# hd-gs-alt.net
KiCad netlist of a schematic drawn in EAGLE
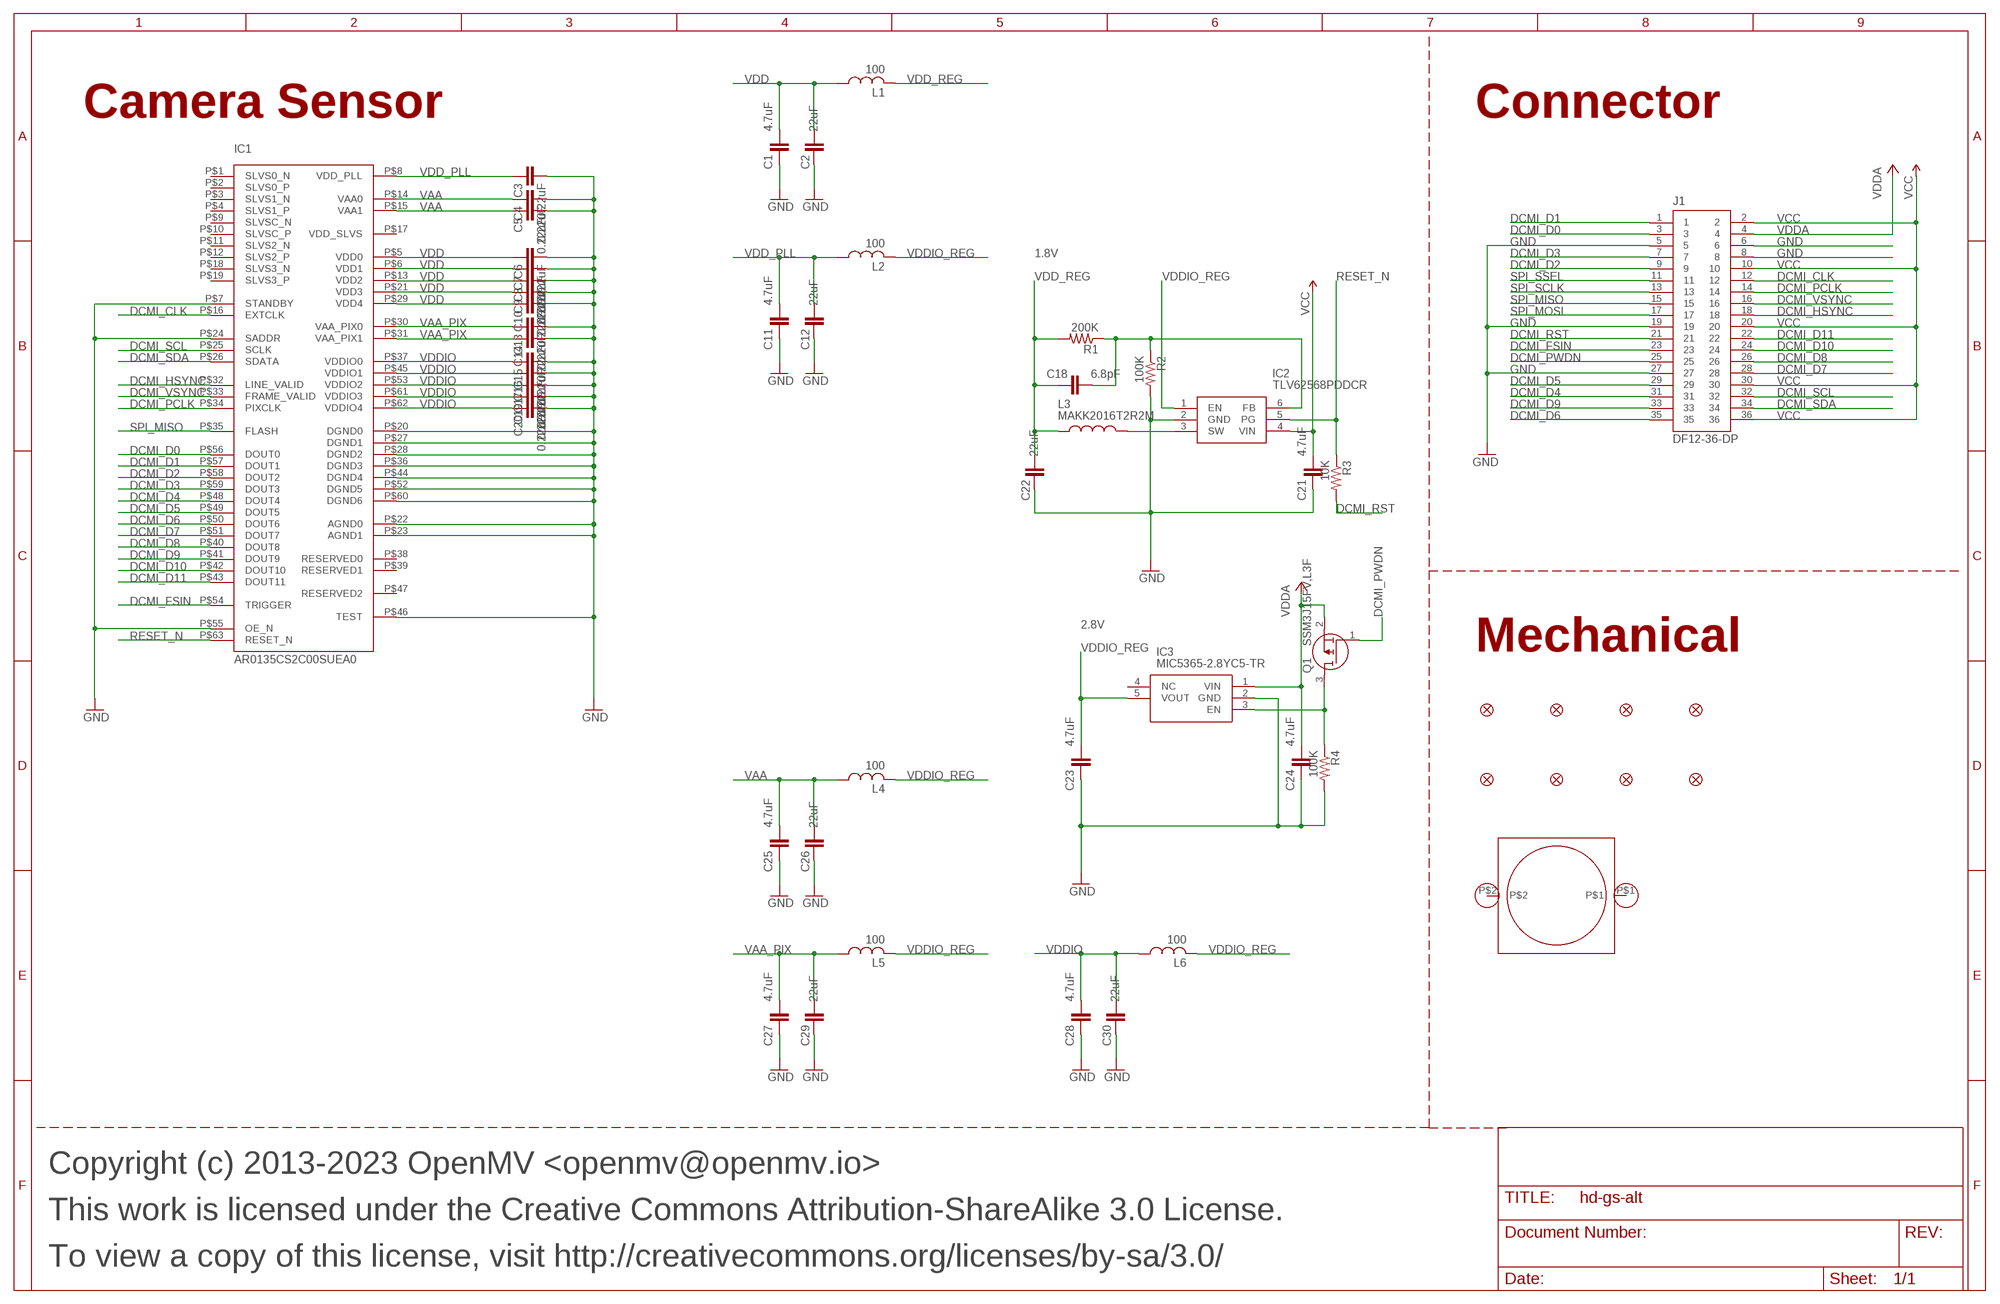
[diagram p0: schematic, sheet 1]

(export (version "E")
  (design (tool "Eeschema 10.0.6"))
  (components
    (comp (ref "C1")
      (value "4.7uF")
      (footprint "eagle-import:0402")
      (fields (field (name "MPN") "JMK105BBJ475MV-F"))
      (libsource (lib "eagle-import") (part "CAP_0402"))
    )
    (comp (ref "C2")
      (value "22uF")
      (footprint "eagle-import:0805")
      (fields (field (name "MPN") "CL21A226MQQNNNE"))
      (libsource (lib "eagle-import") (part "22UF-0805-6.3V-20%"))
    )
    (comp (ref "C3")
      (value "0.22uF")
      (footprint "eagle-import:C0201")
      (fields (field (name "MPN") "GRM033R60J224ME15D"))
      (libsource (lib "eagle-import") (part "C-EUC0201"))
    )
    (comp (ref "C4")
      (value "0.22uF")
      (footprint "eagle-import:C0201")
      (fields (field (name "MPN") "GRM033R60J224ME15D"))
      (libsource (lib "eagle-import") (part "C-EUC0201"))
    )
    (comp (ref "C5")
      (value "0.22uF")
      (footprint "eagle-import:C0201")
      (fields (field (name "MPN") "GRM033R60J224ME15D"))
      (libsource (lib "eagle-import") (part "C-EUC0201"))
    )
    (comp (ref "C6")
      (value "0.22uF")
      (footprint "eagle-import:C0201")
      (fields (field (name "MPN") "GRM033R60J224ME15D"))
      (libsource (lib "eagle-import") (part "C-EUC0201"))
    )
    (comp (ref "C7")
      (value "0.22uF")
      (footprint "eagle-import:C0201")
      (fields (field (name "MPN") "GRM033R60J224ME15D"))
      (libsource (lib "eagle-import") (part "C-EUC0201"))
    )
    (comp (ref "C8")
      (value "0.22uF")
      (footprint "eagle-import:C0201")
      (fields (field (name "MPN") "GRM033R60J224ME15D"))
      (libsource (lib "eagle-import") (part "C-EUC0201"))
    )
    (comp (ref "C9")
      (value "0.22uF")
      (footprint "eagle-import:C0201")
      (fields (field (name "MPN") "GRM033R60J224ME15D"))
      (libsource (lib "eagle-import") (part "C-EUC0201"))
    )
    (comp (ref "C10")
      (value "0.22uF")
      (footprint "eagle-import:C0201")
      (fields (field (name "MPN") "GRM033R60J224ME15D"))
      (libsource (lib "eagle-import") (part "C-EUC0201"))
    )
    (comp (ref "C11")
      (value "4.7uF")
      (footprint "eagle-import:0402")
      (fields (field (name "MPN") "JMK105BBJ475MV-F"))
      (libsource (lib "eagle-import") (part "CAP_0402"))
    )
    (comp (ref "C12")
      (value "22uF")
      (footprint "eagle-import:0805")
      (fields (field (name "MPN") "CL21A226MQQNNNE"))
      (libsource (lib "eagle-import") (part "22UF-0805-6.3V-20%"))
    )
    (comp (ref "C13")
      (value "0.22uF")
      (footprint "eagle-import:C0201")
      (fields (field (name "MPN") "GRM033R60J224ME15D"))
      (libsource (lib "eagle-import") (part "C-EUC0201"))
    )
    (comp (ref "C14")
      (value "0.22uF")
      (footprint "eagle-import:C0201")
      (fields (field (name "MPN") "GRM033R60J224ME15D"))
      (libsource (lib "eagle-import") (part "C-EUC0201"))
    )
    (comp (ref "C15")
      (value "0.22uF")
      (footprint "eagle-import:C0201")
      (fields (field (name "MPN") "GRM033R60J224ME15D"))
      (libsource (lib "eagle-import") (part "C-EUC0201"))
    )
    (comp (ref "C16")
      (value "0.22uF")
      (footprint "eagle-import:C0201")
      (fields (field (name "MPN") "GRM033R60J224ME15D"))
      (libsource (lib "eagle-import") (part "C-EUC0201"))
    )
    (comp (ref "C17")
      (value "0.22uF")
      (footprint "eagle-import:C0201")
      (fields (field (name "MPN") "GRM033R60J224ME15D"))
      (libsource (lib "eagle-import") (part "C-EUC0201"))
    )
    (comp (ref "C18")
      (value "6.8pF")
      (footprint "eagle-import:0402")
      (fields (field (name "MPN") "GRM1555C1H6R8DA01D"))
      (libsource (lib "eagle-import") (part "CAP_0402"))
    )
    (comp (ref "C19")
      (value "0.22uF")
      (footprint "eagle-import:C0201")
      (fields (field (name "MPN") "GRM033R60J224ME15D"))
      (libsource (lib "eagle-import") (part "C-EUC0201"))
    )
    (comp (ref "C20")
      (value "0.22uF")
      (footprint "eagle-import:C0201")
      (fields (field (name "MPN") "GRM033R60J224ME15D"))
      (libsource (lib "eagle-import") (part "C-EUC0201"))
    )
    (comp (ref "C21")
      (value "4.7uF")
      (footprint "eagle-import:0402")
      (fields (field (name "MPN") "JMK105BBJ475MV-F"))
      (libsource (lib "eagle-import") (part "CAP_0402"))
    )
    (comp (ref "C22")
      (value "22uF")
      (footprint "eagle-import:0805")
      (fields (field (name "MPN") "CL21A226MQQNNNE"))
      (libsource (lib "eagle-import") (part "22UF-0805-6.3V-20%"))
    )
    (comp (ref "C23")
      (value "4.7uF")
      (footprint "eagle-import:0402")
      (fields (field (name "MPN") "JMK105BBJ475MV-F"))
      (libsource (lib "eagle-import") (part "CAP_0402"))
    )
    (comp (ref "C24")
      (value "4.7uF")
      (footprint "eagle-import:0402")
      (fields (field (name "MPN") "JMK105BBJ475MV-F"))
      (libsource (lib "eagle-import") (part "CAP_0402"))
    )
    (comp (ref "C25")
      (value "4.7uF")
      (footprint "eagle-import:0402")
      (fields (field (name "MPN") "JMK105BBJ475MV-F"))
      (libsource (lib "eagle-import") (part "CAP_0402"))
    )
    (comp (ref "C26")
      (value "22uF")
      (footprint "eagle-import:0805")
      (fields (field (name "MPN") "CL21A226MQQNNNE"))
      (libsource (lib "eagle-import") (part "22UF-0805-6.3V-20%"))
    )
    (comp (ref "C27")
      (value "4.7uF")
      (footprint "eagle-import:0402")
      (fields (field (name "MPN") "JMK105BBJ475MV-F"))
      (libsource (lib "eagle-import") (part "CAP_0402"))
    )
    (comp (ref "C28")
      (value "4.7uF")
      (footprint "eagle-import:0402")
      (fields (field (name "MPN") "JMK105BBJ475MV-F"))
      (libsource (lib "eagle-import") (part "CAP_0402"))
    )
    (comp (ref "C29")
      (value "22uF")
      (footprint "eagle-import:0805")
      (fields (field (name "MPN") "CL21A226MQQNNNE"))
      (libsource (lib "eagle-import") (part "22UF-0805-6.3V-20%"))
    )
    (comp (ref "C30")
      (value "22uF")
      (footprint "eagle-import:0805")
      (fields (field (name "MPN") "CL21A226MQQNNNE"))
      (libsource (lib "eagle-import") (part "22UF-0805-6.3V-20%"))
    )
    (comp (ref "FD1")
      (value "FIDUCIAL1X2")
      (footprint "eagle-import:FIDUCIAL-1X2")
      (libsource (lib "eagle-import") (part "FIDUCIAL1X2"))
    )
    (comp (ref "FD2")
      (value "FIDUCIAL1X2")
      (footprint "eagle-import:FIDUCIAL-1X2")
      (libsource (lib "eagle-import") (part "FIDUCIAL1X2"))
    )
    (comp (ref "FD3")
      (value "FIDUCIAL1X2")
      (footprint "eagle-import:FIDUCIAL-1X2")
      (libsource (lib "eagle-import") (part "FIDUCIAL1X2"))
    )
    (comp (ref "FD4")
      (value "FIDUCIAL1X2")
      (footprint "eagle-import:FIDUCIAL-1X2")
      (libsource (lib "eagle-import") (part "FIDUCIAL1X2"))
    )
    (comp (ref "FD5")
      (value "FIDUCIAL1X2")
      (footprint "eagle-import:FIDUCIAL-1X2")
      (libsource (lib "eagle-import") (part "FIDUCIAL1X2"))
    )
    (comp (ref "FD6")
      (value "FIDUCIAL1X2")
      (footprint "eagle-import:FIDUCIAL-1X2")
      (libsource (lib "eagle-import") (part "FIDUCIAL1X2"))
    )
    (comp (ref "FD7")
      (value "FIDUCIAL1X2")
      (footprint "eagle-import:FIDUCIAL-1X2")
      (libsource (lib "eagle-import") (part "FIDUCIAL1X2"))
    )
    (comp (ref "FD8")
      (value "FIDUCIAL1X2")
      (footprint "eagle-import:FIDUCIAL-1X2")
      (libsource (lib "eagle-import") (part "FIDUCIAL1X2"))
    )
    (comp (ref "H1")
      (value "LENSMOUNT20MM")
      (footprint "eagle-import:LENSMOUNT-20MM")
      (libsource (lib "eagle-import") (part "LENSMOUNT20MM"))
    )
    (comp (ref "IC1")
      (value "AR0135CS2C00SUEA0")
      (footprint "eagle-import:AR0135CS2C00SUEA0")
      (fields (field (name "MPN") "AR0135CS2C00SUEA0-DRBR"))
      (libsource (lib "eagle-import") (part "AR0135CS2C00SUEA0"))
    )
    (comp (ref "IC2")
      (value "TLV62568PDDCR")
      (footprint "eagle-import:SOT95P280X110-6N")
      (fields (field (name "MOUSER_PART_NUMBER") "595-TLV62568PDDCR"))
      (libsource (lib "eagle-import") (part "TLV62568PDDCR"))
    )
    (comp (ref "IC3")
      (value "MIC5365-2.8YC5-TR")
      (footprint "eagle-import:SOT65P210X110-5N")
      (fields (field (name "MOUSER_PART_NUMBER") "998-MIC5365-2.8YC5TR"))
      (libsource (lib "eagle-import") (part "MIC5365-2.8YC5-TR"))
    )
    (comp (ref "J1")
      (value "DF12-36-DP")
      (footprint "eagle-import:DF12-36-DP")
      (fields (field (name "MPN") "DF12NB(3.0)-36DP-0.5V(51)"))
      (libsource (lib "eagle-import") (part "DF12-36-DP"))
    )
    (comp (ref "L1")
      (value "100")
      (footprint "eagle-import:0402")
      (fields (field (name "MPN") "MFBM1V1005-101-R"))
      (libsource (lib "eagle-import") (part "INDUCTOR_0402"))
    )
    (comp (ref "L2")
      (value "100")
      (footprint "eagle-import:0402")
      (fields (field (name "MPN") "MFBM1V1005-101-R"))
      (libsource (lib "eagle-import") (part "INDUCTOR_0402"))
    )
    (comp (ref "L3")
      (value "MAKK2016T2R2M")
      (footprint "eagle-import:INDC2016X100N")
      (fields (field (name "MF") "Taiyo Yuden"))
      (libsource (lib "eagle-import") (part "MAKK2016T2R2M"))
    )
    (comp (ref "L4")
      (value "100")
      (footprint "eagle-import:0402")
      (fields (field (name "MPN") "MFBM1V1005-101-R"))
      (libsource (lib "eagle-import") (part "INDUCTOR_0402"))
    )
    (comp (ref "L5")
      (value "100")
      (footprint "eagle-import:0402")
      (fields (field (name "MPN") "MFBM1V1005-101-R"))
      (libsource (lib "eagle-import") (part "INDUCTOR_0402"))
    )
    (comp (ref "L6")
      (value "100")
      (footprint "eagle-import:0402")
      (fields (field (name "MPN") "MFBM1V1005-101-R"))
      (libsource (lib "eagle-import") (part "INDUCTOR_0402"))
    )
    (comp (ref "Q1")
      (value "SSM3J15FV,L3F")
      (footprint "eagle-import:SSM3J15FVL3F")
      (fields (field (name "MOUSER_PART_NUMBER") "757-SSM3J15FVL3F"))
      (libsource (lib "eagle-import") (part "SSM3J15FV,L3F"))
    )
    (comp (ref "R1")
      (value "200K")
      (footprint "eagle-import:R0402")
      (fields (field (name "MPN") "CRCW0402200KFKEDC"))
      (libsource (lib "eagle-import") (part "R-US_R0402"))
    )
    (comp (ref "R2")
      (value "100K")
      (footprint "eagle-import:R0402")
      (fields (field (name "MPN") "AC0402FR-07100KL"))
      (libsource (lib "eagle-import") (part "R-US_R0402"))
    )
    (comp (ref "R3")
      (value "10K")
      (footprint "eagle-import:R0402")
      (fields (field (name "MPN") "AC0402FR-1310KL"))
      (libsource (lib "eagle-import") (part "R-US_R0402"))
    )
    (comp (ref "R4")
      (value "100K")
      (footprint "eagle-import:R0402")
      (fields (field (name "MPN") "AC0402FR-07100KL"))
      (libsource (lib "eagle-import") (part "R-US_R0402"))
    )
  )
  (nets
    (net (code "1") (name "/DCMI_CLK") (class "Default")
      (node (ref "IC1") (pin "P$16") (pinfunction "EXTCLK_P$16") (pintype "bidirectional"))
      (node (ref "J1") (pin "12") (pinfunction "12_12") (pintype "bidirectional"))
    )
    (net (code "2") (name "/DCMI_D0") (class "Default")
      (node (ref "IC1") (pin "P$56") (pinfunction "DOUT0_P$56") (pintype "bidirectional"))
      (node (ref "J1") (pin "3") (pinfunction "3_3") (pintype "bidirectional"))
    )
    (net (code "3") (name "/DCMI_D1") (class "Default")
      (node (ref "IC1") (pin "P$57") (pinfunction "DOUT1_P$57") (pintype "bidirectional"))
      (node (ref "J1") (pin "1") (pinfunction "1_1") (pintype "bidirectional"))
    )
    (net (code "4") (name "/DCMI_D2") (class "Default")
      (node (ref "IC1") (pin "P$58") (pinfunction "DOUT2_P$58") (pintype "bidirectional"))
      (node (ref "J1") (pin "9") (pinfunction "9_9") (pintype "bidirectional"))
    )
    (net (code "5") (name "/DCMI_D3") (class "Default")
      (node (ref "IC1") (pin "P$59") (pinfunction "DOUT3_P$59") (pintype "bidirectional"))
      (node (ref "J1") (pin "7") (pinfunction "7_7") (pintype "bidirectional"))
    )
    (net (code "6") (name "/DCMI_D4") (class "Default")
      (node (ref "IC1") (pin "P$48") (pinfunction "DOUT4_P$48") (pintype "bidirectional"))
      (node (ref "J1") (pin "31") (pinfunction "31_31") (pintype "bidirectional"))
    )
    (net (code "7") (name "/DCMI_D5") (class "Default")
      (node (ref "IC1") (pin "P$49") (pinfunction "DOUT5_P$49") (pintype "bidirectional"))
      (node (ref "J1") (pin "29") (pinfunction "29_29") (pintype "bidirectional"))
    )
    (net (code "8") (name "/DCMI_D6") (class "Default")
      (node (ref "IC1") (pin "P$50") (pinfunction "DOUT6_P$50") (pintype "bidirectional"))
      (node (ref "J1") (pin "35") (pinfunction "35_35") (pintype "bidirectional"))
    )
    (net (code "9") (name "/DCMI_D7") (class "Default")
      (node (ref "IC1") (pin "P$51") (pinfunction "DOUT7_P$51") (pintype "bidirectional"))
      (node (ref "J1") (pin "28") (pinfunction "28_28") (pintype "bidirectional"))
    )
    (net (code "10") (name "/DCMI_D8") (class "Default")
      (node (ref "IC1") (pin "P$40") (pinfunction "DOUT8_P$40") (pintype "bidirectional"))
      (node (ref "J1") (pin "26") (pinfunction "26_26") (pintype "bidirectional"))
    )
    (net (code "11") (name "/DCMI_D9") (class "Default")
      (node (ref "IC1") (pin "P$41") (pinfunction "DOUT9_P$41") (pintype "bidirectional"))
      (node (ref "J1") (pin "33") (pinfunction "33_33") (pintype "bidirectional"))
    )
    (net (code "12") (name "/DCMI_D10") (class "Default")
      (node (ref "IC1") (pin "P$42") (pinfunction "DOUT10_P$42") (pintype "bidirectional"))
      (node (ref "J1") (pin "24") (pinfunction "24_24") (pintype "bidirectional"))
    )
    (net (code "13") (name "/DCMI_D11") (class "Default")
      (node (ref "IC1") (pin "P$43") (pinfunction "DOUT11_P$43") (pintype "bidirectional"))
      (node (ref "J1") (pin "22") (pinfunction "22_22") (pintype "bidirectional"))
    )
    (net (code "14") (name "/DCMI_FSIN") (class "Default")
      (node (ref "IC1") (pin "P$54") (pinfunction "TRIGGER_P$54") (pintype "bidirectional"))
      (node (ref "J1") (pin "23") (pinfunction "23_23") (pintype "bidirectional"))
    )
    (net (code "15") (name "/DCMI_HSYNC") (class "Default")
      (node (ref "IC1") (pin "P$32") (pinfunction "LINE_VALID_P$32") (pintype "bidirectional"))
      (node (ref "J1") (pin "18") (pinfunction "18_18") (pintype "bidirectional"))
    )
    (net (code "16") (name "/DCMI_PCLK") (class "Default")
      (node (ref "IC1") (pin "P$34") (pinfunction "PIXCLK_P$34") (pintype "bidirectional"))
      (node (ref "J1") (pin "14") (pinfunction "14_14") (pintype "bidirectional"))
    )
    (net (code "17") (name "/DCMI_PWDN") (class "Default")
      (node (ref "J1") (pin "25") (pinfunction "25_25") (pintype "bidirectional"))
      (node (ref "Q1") (pin "1") (pinfunction "G_1") (pintype "bidirectional"))
    )
    (net (code "18") (name "/DCMI_RST") (class "Default")
      (node (ref "J1") (pin "21") (pinfunction "21_21") (pintype "bidirectional"))
      (node (ref "R3") (pin "2") (pinfunction "2_2") (pintype "passive"))
    )
    (net (code "19") (name "/DCMI_SCL") (class "Default")
      (node (ref "IC1") (pin "P$25") (pinfunction "SCLK_P$25") (pintype "bidirectional"))
      (node (ref "J1") (pin "32") (pinfunction "32_32") (pintype "bidirectional"))
    )
    (net (code "20") (name "/DCMI_SDA") (class "Default")
      (node (ref "IC1") (pin "P$26") (pinfunction "SDATA_P$26") (pintype "bidirectional"))
      (node (ref "J1") (pin "34") (pinfunction "34_34") (pintype "bidirectional"))
    )
    (net (code "21") (name "/DCMI_VSYNC") (class "Default")
      (node (ref "IC1") (pin "P$33") (pinfunction "FRAME_VALID_P$33") (pintype "bidirectional"))
      (node (ref "J1") (pin "16") (pinfunction "16_16") (pintype "bidirectional"))
    )
    (net (code "22") (name "/P$1") (class "Default")
      (node (ref "H1") (pin "P$1") (pinfunction "P$1_P$1") (pintype "power_in"))
    )
    (net (code "23") (name "/P$2") (class "Default")
      (node (ref "H1") (pin "P$2") (pinfunction "P$2_P$2") (pintype "power_in"))
    )
    (net (code "24") (name "/RESET_N") (class "Default")
      (node (ref "IC1") (pin "P$63") (pinfunction "RESET_N_P$63") (pintype "bidirectional"))
      (node (ref "IC2") (pin "5") (pinfunction "PG_5") (pintype "bidirectional"))
      (node (ref "R3") (pin "1") (pinfunction "1_1") (pintype "passive"))
    )
    (net (code "25") (name "/SPI_MISO") (class "Default")
      (node (ref "IC1") (pin "P$35") (pinfunction "FLASH_P$35") (pintype "bidirectional"))
      (node (ref "J1") (pin "15") (pinfunction "15_15") (pintype "bidirectional"))
    )
    (net (code "26") (name "/SPI_MOSI") (class "Default")
      (node (ref "J1") (pin "17") (pinfunction "17_17") (pintype "bidirectional"))
    )
    (net (code "27") (name "/SPI_SCLK") (class "Default")
      (node (ref "J1") (pin "13") (pinfunction "13_13") (pintype "bidirectional"))
    )
    (net (code "28") (name "/SPI_SSEL") (class "Default")
      (node (ref "J1") (pin "11") (pinfunction "11_11") (pintype "bidirectional"))
    )
    (net (code "29") (name "/VAA") (class "Default")
      (node (ref "C25") (pin "2") (pinfunction "2_2") (pintype "passive"))
      (node (ref "C26") (pin "2") (pinfunction "2_2") (pintype "passive"))
      (node (ref "C4") (pin "1") (pinfunction "1_1") (pintype "passive"))
      (node (ref "C5") (pin "1") (pinfunction "1_1") (pintype "passive"))
      (node (ref "IC1") (pin "P$14") (pinfunction "VAA0_P$14") (pintype "bidirectional"))
      (node (ref "IC1") (pin "P$15") (pinfunction "VAA1_P$15") (pintype "bidirectional"))
      (node (ref "L4") (pin "1") (pinfunction "P$1_1") (pintype "passive"))
    )
    (net (code "30") (name "/VAA_PIX") (class "Default")
      (node (ref "C13") (pin "1") (pinfunction "1_1") (pintype "passive"))
      (node (ref "C14") (pin "1") (pinfunction "1_1") (pintype "passive"))
      (node (ref "C27") (pin "2") (pinfunction "2_2") (pintype "passive"))
      (node (ref "C29") (pin "2") (pinfunction "2_2") (pintype "passive"))
      (node (ref "IC1") (pin "P$30") (pinfunction "VAA_PIX0_P$30") (pintype "bidirectional"))
      (node (ref "IC1") (pin "P$31") (pinfunction "VAA_PIX1_P$31") (pintype "bidirectional"))
      (node (ref "L5") (pin "1") (pinfunction "P$1_1") (pintype "passive"))
    )
    (net (code "31") (name "/VDD") (class "Default")
      (node (ref "C1") (pin "2") (pinfunction "2_2") (pintype "passive"))
      (node (ref "C10") (pin "1") (pinfunction "1_1") (pintype "passive"))
      (node (ref "C2") (pin "2") (pinfunction "2_2") (pintype "passive"))
      (node (ref "C6") (pin "1") (pinfunction "1_1") (pintype "passive"))
      (node (ref "C7") (pin "1") (pinfunction "1_1") (pintype "passive"))
      (node (ref "C8") (pin "1") (pinfunction "1_1") (pintype "passive"))
      (node (ref "C9") (pin "1") (pinfunction "1_1") (pintype "passive"))
      (node (ref "IC1") (pin "P$13") (pinfunction "VDD2_P$13") (pintype "bidirectional"))
      (node (ref "IC1") (pin "P$21") (pinfunction "VDD3_P$21") (pintype "bidirectional"))
      (node (ref "IC1") (pin "P$29") (pinfunction "VDD4_P$29") (pintype "bidirectional"))
      (node (ref "IC1") (pin "P$5") (pinfunction "VDD0_P$5") (pintype "bidirectional"))
      (node (ref "IC1") (pin "P$6") (pinfunction "VDD1_P$6") (pintype "bidirectional"))
      (node (ref "L1") (pin "1") (pinfunction "P$1_1") (pintype "passive"))
    )
    (net (code "32") (name "/VDDIO") (class "Default")
      (node (ref "C15") (pin "1") (pinfunction "1_1") (pintype "passive"))
      (node (ref "C16") (pin "1") (pinfunction "1_1") (pintype "passive"))
      (node (ref "C17") (pin "1") (pinfunction "1_1") (pintype "passive"))
      (node (ref "C19") (pin "1") (pinfunction "1_1") (pintype "passive"))
      (node (ref "C20") (pin "1") (pinfunction "1_1") (pintype "passive"))
      (node (ref "C28") (pin "2") (pinfunction "2_2") (pintype "passive"))
      (node (ref "C30") (pin "2") (pinfunction "2_2") (pintype "passive"))
      (node (ref "IC1") (pin "P$37") (pinfunction "VDDIO0_P$37") (pintype "bidirectional"))
      (node (ref "IC1") (pin "P$45") (pinfunction "VDDIO1_P$45") (pintype "bidirectional"))
      (node (ref "IC1") (pin "P$53") (pinfunction "VDDIO2_P$53") (pintype "bidirectional"))
      (node (ref "IC1") (pin "P$61") (pinfunction "VDDIO3_P$61") (pintype "bidirectional"))
      (node (ref "IC1") (pin "P$62") (pinfunction "VDDIO4_P$62") (pintype "bidirectional"))
      (node (ref "L6") (pin "1") (pinfunction "P$1_1") (pintype "passive"))
    )
    (net (code "33") (name "/VDDIO_REG") (class "Default")
      (node (ref "C23") (pin "2") (pinfunction "2_2") (pintype "passive"))
      (node (ref "IC2") (pin "1") (pinfunction "EN_1") (pintype "bidirectional"))
      (node (ref "IC3") (pin "5") (pinfunction "VOUT_5") (pintype "bidirectional"))
      (node (ref "L2") (pin "2") (pinfunction "P$2_2") (pintype "passive"))
      (node (ref "L4") (pin "2") (pinfunction "P$2_2") (pintype "passive"))
      (node (ref "L5") (pin "2") (pinfunction "P$2_2") (pintype "passive"))
      (node (ref "L6") (pin "2") (pinfunction "P$2_2") (pintype "passive"))
    )
    (net (code "34") (name "/VDD_PLL") (class "Default")
      (node (ref "C11") (pin "2") (pinfunction "2_2") (pintype "passive"))
      (node (ref "C12") (pin "2") (pinfunction "2_2") (pintype "passive"))
      (node (ref "C3") (pin "1") (pinfunction "1_1") (pintype "passive"))
      (node (ref "IC1") (pin "P$8") (pinfunction "VDD_PLL_P$8") (pintype "bidirectional"))
      (node (ref "L2") (pin "1") (pinfunction "P$1_1") (pintype "passive"))
    )
    (net (code "35") (name "/VDD_REG") (class "Default")
      (node (ref "C18") (pin "1") (pinfunction "1_1") (pintype "passive"))
      (node (ref "C22") (pin "2") (pinfunction "2_2") (pintype "passive"))
      (node (ref "L1") (pin "2") (pinfunction "P$2_2") (pintype "passive"))
      (node (ref "L3") (pin "1") (pinfunction "1_1") (pintype "passive"))
      (node (ref "R1") (pin "2") (pinfunction "2_2") (pintype "passive"))
    )
    (net (code "36") (name "GND") (class "Default")
      (node (ref "C1") (pin "1") (pinfunction "1_1") (pintype "passive"))
      (node (ref "C10") (pin "2") (pinfunction "2_2") (pintype "passive"))
      (node (ref "C11") (pin "1") (pinfunction "1_1") (pintype "passive"))
      (node (ref "C12") (pin "1") (pinfunction "1_1") (pintype "passive"))
      (node (ref "C13") (pin "2") (pinfunction "2_2") (pintype "passive"))
      (node (ref "C14") (pin "2") (pinfunction "2_2") (pintype "passive"))
      (node (ref "C15") (pin "2") (pinfunction "2_2") (pintype "passive"))
      (node (ref "C16") (pin "2") (pinfunction "2_2") (pintype "passive"))
      (node (ref "C17") (pin "2") (pinfunction "2_2") (pintype "passive"))
      (node (ref "C19") (pin "2") (pinfunction "2_2") (pintype "passive"))
      (node (ref "C2") (pin "1") (pinfunction "1_1") (pintype "passive"))
      (node (ref "C20") (pin "2") (pinfunction "2_2") (pintype "passive"))
      (node (ref "C21") (pin "1") (pinfunction "1_1") (pintype "passive"))
      (node (ref "C22") (pin "1") (pinfunction "1_1") (pintype "passive"))
      (node (ref "C23") (pin "1") (pinfunction "1_1") (pintype "passive"))
      (node (ref "C24") (pin "1") (pinfunction "1_1") (pintype "passive"))
      (node (ref "C25") (pin "1") (pinfunction "1_1") (pintype "passive"))
      (node (ref "C26") (pin "1") (pinfunction "1_1") (pintype "passive"))
      (node (ref "C27") (pin "1") (pinfunction "1_1") (pintype "passive"))
      (node (ref "C28") (pin "1") (pinfunction "1_1") (pintype "passive"))
      (node (ref "C29") (pin "1") (pinfunction "1_1") (pintype "passive"))
      (node (ref "C3") (pin "2") (pinfunction "2_2") (pintype "passive"))
      (node (ref "C30") (pin "1") (pinfunction "1_1") (pintype "passive"))
      (node (ref "C4") (pin "2") (pinfunction "2_2") (pintype "passive"))
      (node (ref "C5") (pin "2") (pinfunction "2_2") (pintype "passive"))
      (node (ref "C6") (pin "2") (pinfunction "2_2") (pintype "passive"))
      (node (ref "C7") (pin "2") (pinfunction "2_2") (pintype "passive"))
      (node (ref "C8") (pin "2") (pinfunction "2_2") (pintype "passive"))
      (node (ref "C9") (pin "2") (pinfunction "2_2") (pintype "passive"))
      (node (ref "IC1") (pin "P$20") (pinfunction "DGND0_P$20") (pintype "bidirectional"))
      (node (ref "IC1") (pin "P$22") (pinfunction "AGND0_P$22") (pintype "bidirectional"))
      (node (ref "IC1") (pin "P$23") (pinfunction "AGND1_P$23") (pintype "bidirectional"))
      (node (ref "IC1") (pin "P$24") (pinfunction "SADDR_P$24") (pintype "bidirectional"))
      (node (ref "IC1") (pin "P$27") (pinfunction "DGND1_P$27") (pintype "bidirectional"))
      (node (ref "IC1") (pin "P$28") (pinfunction "DGND2_P$28") (pintype "bidirectional"))
      (node (ref "IC1") (pin "P$36") (pinfunction "DGND3_P$36") (pintype "bidirectional"))
      (node (ref "IC1") (pin "P$44") (pinfunction "DGND4_P$44") (pintype "bidirectional"))
      (node (ref "IC1") (pin "P$46") (pinfunction "TEST_P$46") (pintype "bidirectional"))
      (node (ref "IC1") (pin "P$52") (pinfunction "DGND5_P$52") (pintype "bidirectional"))
      (node (ref "IC1") (pin "P$55") (pinfunction "OE_N_P$55") (pintype "bidirectional"))
      (node (ref "IC1") (pin "P$60") (pinfunction "DGND6_P$60") (pintype "bidirectional"))
      (node (ref "IC1") (pin "P$7") (pinfunction "STANDBY_P$7") (pintype "bidirectional"))
      (node (ref "IC2") (pin "2") (pinfunction "GND_2") (pintype "bidirectional"))
      (node (ref "IC3") (pin "2") (pinfunction "GND_2") (pintype "bidirectional"))
      (node (ref "J1") (pin "19") (pinfunction "19_19") (pintype "bidirectional"))
      (node (ref "J1") (pin "27") (pinfunction "27_27") (pintype "bidirectional"))
      (node (ref "J1") (pin "5") (pinfunction "5_5") (pintype "bidirectional"))
      (node (ref "J1") (pin "6") (pinfunction "6_6") (pintype "bidirectional"))
      (node (ref "J1") (pin "8") (pinfunction "8_8") (pintype "bidirectional"))
      (node (ref "R2") (pin "2") (pinfunction "2_2") (pintype "passive"))
      (node (ref "R4") (pin "2") (pinfunction "2_2") (pintype "passive"))
    )
    (net (code "37") (name "Net-(IC2-FB)") (class "Default")
      (node (ref "C18") (pin "2") (pinfunction "2_2") (pintype "passive"))
      (node (ref "IC2") (pin "6") (pinfunction "FB_6") (pintype "bidirectional"))
      (node (ref "R1") (pin "1") (pinfunction "1_1") (pintype "passive"))
      (node (ref "R2") (pin "1") (pinfunction "1_1") (pintype "passive"))
    )
    (net (code "38") (name "Net-(IC2-SW)") (class "Default")
      (node (ref "IC2") (pin "3") (pinfunction "SW_3") (pintype "bidirectional"))
      (node (ref "L3") (pin "2") (pinfunction "2_2") (pintype "passive"))
    )
    (net (code "39") (name "Net-(IC3-EN)") (class "Default")
      (node (ref "IC3") (pin "3") (pinfunction "EN_3") (pintype "bidirectional"))
      (node (ref "Q1") (pin "3") (pinfunction "D_3") (pintype "bidirectional"))
      (node (ref "R4") (pin "1") (pinfunction "1_1") (pintype "passive"))
    )
    (net (code "40") (name "VCC") (class "Default")
      (node (ref "C21") (pin "2") (pinfunction "2_2") (pintype "passive"))
      (node (ref "IC2") (pin "4") (pinfunction "VIN_4") (pintype "bidirectional"))
      (node (ref "J1") (pin "10") (pinfunction "10_10") (pintype "bidirectional"))
      (node (ref "J1") (pin "2") (pinfunction "2_2") (pintype "bidirectional"))
      (node (ref "J1") (pin "20") (pinfunction "20_20") (pintype "bidirectional"))
      (node (ref "J1") (pin "30") (pinfunction "30_30") (pintype "bidirectional"))
      (node (ref "J1") (pin "36") (pinfunction "36_36") (pintype "bidirectional"))
    )
    (net (code "41") (name "VDDA") (class "Default")
      (node (ref "C24") (pin "2") (pinfunction "2_2") (pintype "passive"))
      (node (ref "IC3") (pin "1") (pinfunction "VIN_1") (pintype "bidirectional"))
      (node (ref "J1") (pin "4") (pinfunction "4_4") (pintype "bidirectional"))
      (node (ref "Q1") (pin "2") (pinfunction "S_2") (pintype "bidirectional"))
    )
    (net (code "42") (name "unconnected-(IC1-RESERVED0-PadP$38)") (class "Default")
      (node (ref "IC1") (pin "P$38") (pinfunction "RESERVED0_P$38") (pintype "bidirectional"))
    )
    (net (code "43") (name "unconnected-(IC1-RESERVED1-PadP$39)") (class "Default")
      (node (ref "IC1") (pin "P$39") (pinfunction "RESERVED1_P$39") (pintype "bidirectional"))
    )
    (net (code "44") (name "unconnected-(IC1-RESERVED2-PadP$47)") (class "Default")
      (node (ref "IC1") (pin "P$47") (pinfunction "RESERVED2_P$47") (pintype "bidirectional"))
    )
    (net (code "45") (name "unconnected-(IC1-SLVS0_N-PadP$1)") (class "Default")
      (node (ref "IC1") (pin "P$1") (pinfunction "SLVS0_N_P$1") (pintype "bidirectional"))
    )
    (net (code "46") (name "unconnected-(IC1-SLVS0_P-PadP$2)") (class "Default")
      (node (ref "IC1") (pin "P$2") (pinfunction "SLVS0_P_P$2") (pintype "bidirectional"))
    )
    (net (code "47") (name "unconnected-(IC1-SLVS1_N-PadP$3)") (class "Default")
      (node (ref "IC1") (pin "P$3") (pinfunction "SLVS1_N_P$3") (pintype "bidirectional"))
    )
    (net (code "48") (name "unconnected-(IC1-SLVS1_P-PadP$4)") (class "Default")
      (node (ref "IC1") (pin "P$4") (pinfunction "SLVS1_P_P$4") (pintype "bidirectional"))
    )
    (net (code "49") (name "unconnected-(IC1-SLVS2_N-PadP$11)") (class "Default")
      (node (ref "IC1") (pin "P$11") (pinfunction "SLVS2_N_P$11") (pintype "bidirectional"))
    )
    (net (code "50") (name "unconnected-(IC1-SLVS2_P-PadP$12)") (class "Default")
      (node (ref "IC1") (pin "P$12") (pinfunction "SLVS2_P_P$12") (pintype "bidirectional"))
    )
    (net (code "51") (name "unconnected-(IC1-SLVS3_N-PadP$18)") (class "Default")
      (node (ref "IC1") (pin "P$18") (pinfunction "SLVS3_N_P$18") (pintype "bidirectional"))
    )
    (net (code "52") (name "unconnected-(IC1-SLVS3_P-PadP$19)") (class "Default")
      (node (ref "IC1") (pin "P$19") (pinfunction "SLVS3_P_P$19") (pintype "bidirectional"))
    )
    (net (code "53") (name "unconnected-(IC1-SLVSC_N-PadP$9)") (class "Default")
      (node (ref "IC1") (pin "P$9") (pinfunction "SLVSC_N_P$9") (pintype "bidirectional"))
    )
    (net (code "54") (name "unconnected-(IC1-SLVSC_P-PadP$10)") (class "Default")
      (node (ref "IC1") (pin "P$10") (pinfunction "SLVSC_P_P$10") (pintype "bidirectional"))
    )
    (net (code "55") (name "unconnected-(IC1-VDD_SLVS-PadP$17)") (class "Default")
      (node (ref "IC1") (pin "P$17") (pinfunction "VDD_SLVS_P$17") (pintype "bidirectional"))
    )
    (net (code "56") (name "unconnected-(IC3-NC-Pad4)") (class "Default")
      (node (ref "IC3") (pin "4") (pinfunction "NC_4") (pintype "no_connect"))
    )
  )
)
